# SCH_USB_hub_2024-10-12.net
KiCad netlist of a schematic drawn in EasyEDA
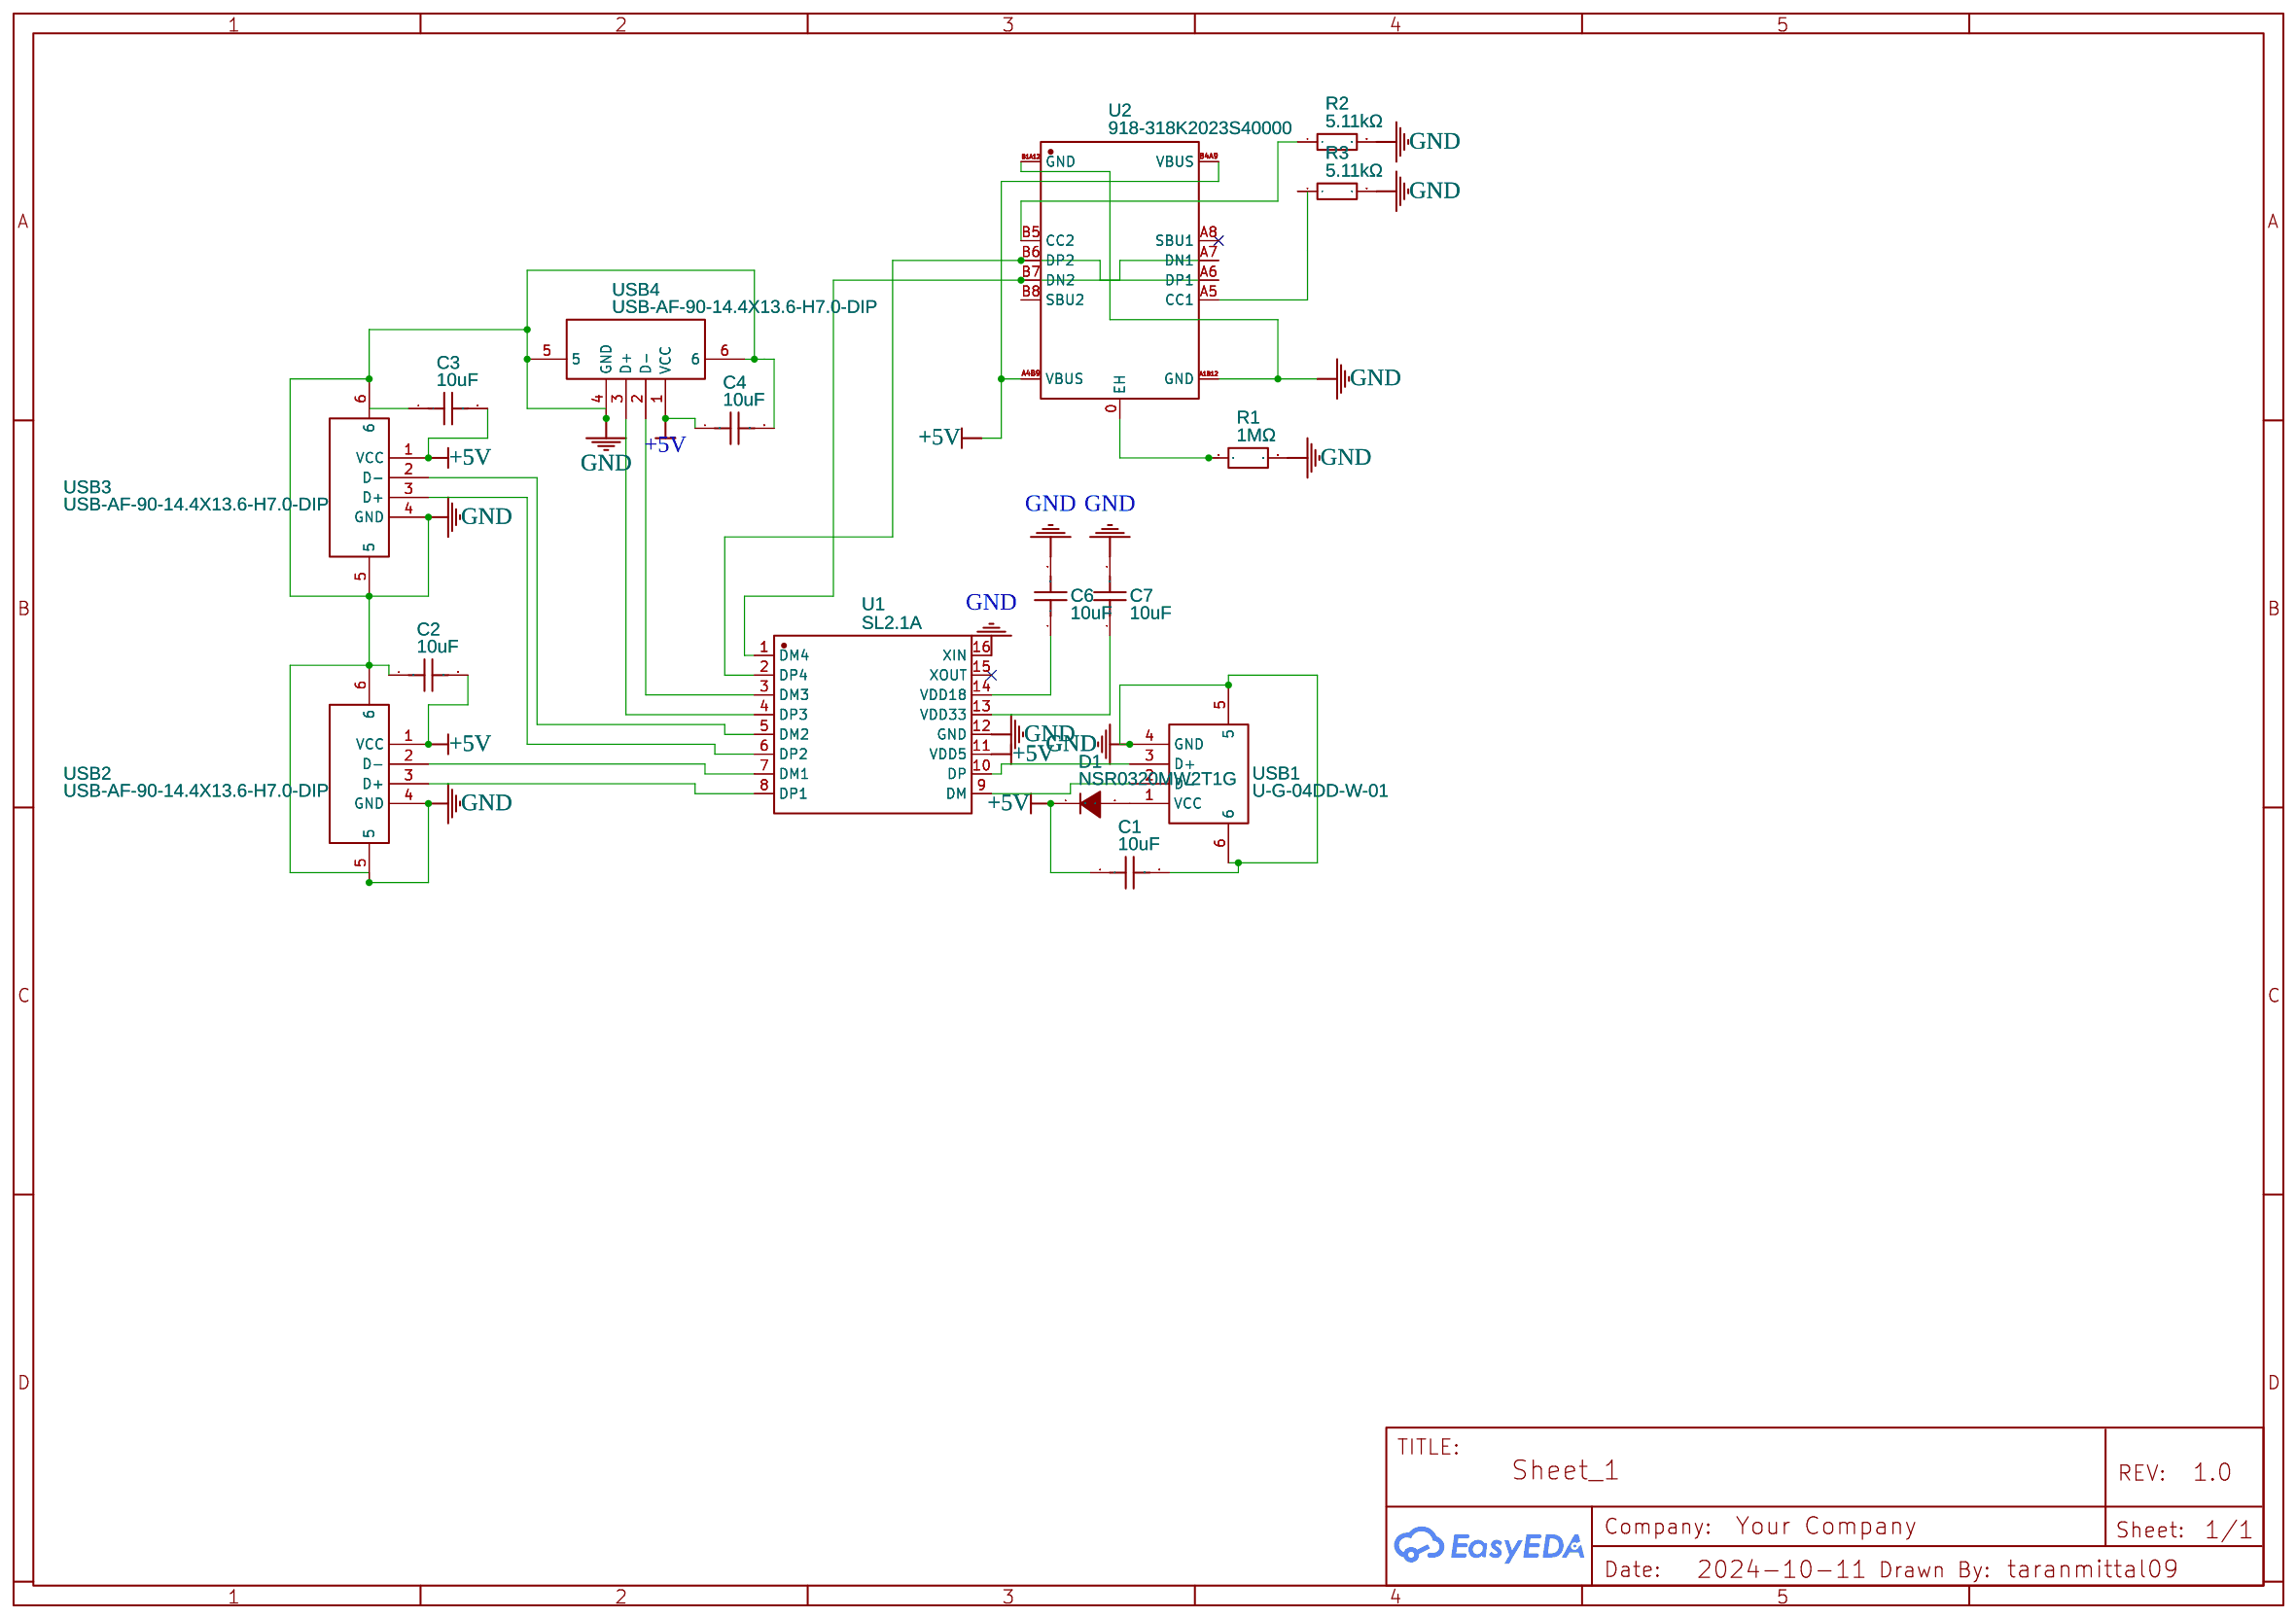
[diagram p0: schematic sheet]

(export (version "E")
  (design (tool "Eeschema 10.0.6"))
  (components
    (comp (ref "C1")
      (value "10uF")
      (fields
        (field (name "Manufacturer Part") "CL10A106KP8NNNC")
        (field (name "Manufacturer") "SAMSUNG(三星)")
      )
      (libsource (lib "") (part "CL10A106KP8NNNC"))
    )
    (comp (ref "C2")
      (value "10uF")
      (fields
        (field (name "Manufacturer Part") "CL10A106KP8NNNC")
        (field (name "Manufacturer") "SAMSUNG(三星)")
      )
      (libsource (lib "") (part "CL10A106KP8NNNC"))
    )
    (comp (ref "C3")
      (value "10uF")
      (fields
        (field (name "Manufacturer Part") "CL10A106KP8NNNC")
        (field (name "Manufacturer") "SAMSUNG(三星)")
      )
      (libsource (lib "") (part "CL10A106KP8NNNC"))
    )
    (comp (ref "C4")
      (value "10uF")
      (fields
        (field (name "Manufacturer Part") "CL10A106KP8NNNC")
        (field (name "Manufacturer") "SAMSUNG(三星)")
      )
      (libsource (lib "") (part "CL10A106KP8NNNC"))
    )
    (comp (ref "C6")
      (value "10uF")
      (fields
        (field (name "Manufacturer Part") "CL10A106KP8NNNC")
        (field (name "Manufacturer") "SAMSUNG(三星)")
      )
      (libsource (lib "") (part "CL10A106KP8NNNC_1"))
    )
    (comp (ref "C7")
      (value "10uF")
      (fields
        (field (name "Manufacturer Part") "CL10A106KP8NNNC")
        (field (name "Manufacturer") "SAMSUNG(三星)")
      )
      (libsource (lib "") (part "CL10A106KP8NNNC_1"))
    )
    (comp (ref "D1")
      (value "NSR0320MW2T1G")
      (fields (field (name "Manufacturer") "onsemi(安森美)"))
      (libsource (lib "") (part "NSR0320MW2T1G"))
    )
    (comp (ref "R1")
      (value "1MΩ")
      (fields
        (field (name "Manufacturer Part") "CRCW08051M00FKTB")
        (field (name "Manufacturer") "VISHAY(威世)")
      )
      (libsource (lib "") (part "CRCW08051M00FKTB"))
    )
    (comp (ref "R2")
      (value "5.11kΩ")
      (fields (field (name "Manufacturer Part") "RS-03K5111FT") (field (name "Manufacturer") "FH(风华)"))
      (libsource (lib "") (part "RS-03K5111FT"))
    )
    (comp (ref "R3")
      (value "5.11kΩ")
      (fields (field (name "Manufacturer Part") "RS-03K5111FT") (field (name "Manufacturer") "FH(风华)"))
      (libsource (lib "") (part "RS-03K5111FT"))
    )
    (comp (ref "U1")
      (value "SL2.1A")
      (fields (field (name "Manufacturer") "CoreChips(和芯润德)"))
      (libsource (lib "") (part "SL2.1A"))
    )
    (comp (ref "U2")
      (value "918-318K2023S40000")
      (fields (field (name "Manufacturer") "精拓金"))
      (libsource (lib "") (part "918-318K2023S40000"))
    )
    (comp (ref "USB1")
      (value "U-G-04DD-W-01")
      (fields (field (name "Manufacturer Part") "U-G-O4DD-W-1") (field (name "Manufacturer") "韩国韩荣"))
      (libsource (lib "") (part "U-G-04DD-W-01"))
    )
    (comp (ref "USB2")
      (value "USB-AF-90-14.4X13.6-H7.0-DIP")
      (fields (field (name "Manufacturer Part") "903-131A1011D10100") (field (name "Manufacturer") "精拓金"))
      (libsource (lib "") (part "USB-AF-90-14.4X13.6-H7.0-DIP"))
    )
    (comp (ref "USB3")
      (value "USB-AF-90-14.4X13.6-H7.0-DIP")
      (fields (field (name "Manufacturer Part") "903-131A1011D10100") (field (name "Manufacturer") "精拓金"))
      (libsource (lib "") (part "USB-AF-90-14.4X13.6-H7.0-DIP"))
    )
    (comp (ref "USB4")
      (value "USB-AF-90-14.4X13.6-H7.0-DIP")
      (fields (field (name "Manufacturer Part") "903-131A1011D10100") (field (name "Manufacturer") "精拓金"))
      (libsource (lib "") (part "USB-AF-90-14.4X13.6-H7.0-DIP_1"))
    )
  )
  (nets
    (net (code "1") (name "+5V") (class "Default")
      (node (ref "C1") (pin "1") (pinfunction "1_1") (pintype "unspecified"))
      (node (ref "C2") (pin "2") (pinfunction "2_2") (pintype "unspecified"))
      (node (ref "C3") (pin "2") (pinfunction "2_2") (pintype "unspecified"))
      (node (ref "C4") (pin "1") (pinfunction "1_1") (pintype "unspecified"))
      (node (ref "D1") (pin "1") (pinfunction "C_1") (pintype "unspecified"))
      (node (ref "U1") (pin "11") (pinfunction "VDD5_11") (pintype "unspecified"))
      (node (ref "U2") (pin "A4B9") (pinfunction "VBUS_A4B9") (pintype "unspecified"))
      (node (ref "U2") (pin "B4A9") (pinfunction "VBUS_B4A9") (pintype "unspecified"))
      (node (ref "USB2") (pin "1") (pinfunction "VCC_1") (pintype "unspecified"))
      (node (ref "USB3") (pin "1") (pinfunction "VCC_1") (pintype "unspecified"))
      (node (ref "USB4") (pin "1") (pinfunction "VCC_1") (pintype "unspecified"))
    )
    (net (code "2") (name "GND") (class "Default")
      (node (ref "C1") (pin "2") (pinfunction "2_2") (pintype "unspecified"))
      (node (ref "C2") (pin "1") (pinfunction "1_1") (pintype "unspecified"))
      (node (ref "C3") (pin "1") (pinfunction "1_1") (pintype "unspecified"))
      (node (ref "C4") (pin "2") (pinfunction "2_2") (pintype "unspecified"))
      (node (ref "C6") (pin "2") (pinfunction "2_2") (pintype "unspecified"))
      (node (ref "C7") (pin "2") (pinfunction "2_2") (pintype "unspecified"))
      (node (ref "R1") (pin "2") (pinfunction "2_2") (pintype "unspecified"))
      (node (ref "R2") (pin "2") (pinfunction "2_2") (pintype "input"))
      (node (ref "R3") (pin "2") (pinfunction "2_2") (pintype "input"))
      (node (ref "U1") (pin "12") (pinfunction "GND_12") (pintype "unspecified"))
      (node (ref "U1") (pin "16") (pinfunction "XIN_16") (pintype "unspecified"))
      (node (ref "U2") (pin "A1B12") (pinfunction "GND_A1B12") (pintype "unspecified"))
      (node (ref "U2") (pin "B1A12") (pinfunction "GND_B1A12") (pintype "unspecified"))
      (node (ref "USB1") (pin "4") (pinfunction "GND_4") (pintype "unspecified"))
      (node (ref "USB1") (pin "5") (pinfunction "5_5") (pintype "unspecified"))
      (node (ref "USB1") (pin "6") (pinfunction "6_6") (pintype "unspecified"))
      (node (ref "USB2") (pin "4") (pinfunction "GND_4") (pintype "unspecified"))
      (node (ref "USB2") (pin "5") (pinfunction "5_5") (pintype "unspecified"))
      (node (ref "USB2") (pin "6") (pinfunction "6_6") (pintype "unspecified"))
      (node (ref "USB3") (pin "4") (pinfunction "GND_4") (pintype "unspecified"))
      (node (ref "USB3") (pin "5") (pinfunction "5_5") (pintype "unspecified"))
      (node (ref "USB3") (pin "6") (pinfunction "6_6") (pintype "unspecified"))
      (node (ref "USB4") (pin "4") (pinfunction "GND_4") (pintype "unspecified"))
      (node (ref "USB4") (pin "5") (pinfunction "5_5") (pintype "unspecified"))
      (node (ref "USB4") (pin "6") (pinfunction "6_6") (pintype "unspecified"))
    )
    (net (code "3") (name "Net-(D1-A)") (class "Default")
      (node (ref "D1") (pin "2") (pinfunction "A_2") (pintype "unspecified"))
      (node (ref "USB1") (pin "1") (pinfunction "VCC_1") (pintype "unspecified"))
    )
    (net (code "4") (name "Net-(U1-DM)") (class "Default")
      (node (ref "U1") (pin "9") (pinfunction "DM_9") (pintype "unspecified"))
      (node (ref "USB1") (pin "2") (pinfunction "D-_2") (pintype "unspecified"))
    )
    (net (code "5") (name "Net-(U1-DM1)") (class "Default")
      (node (ref "U1") (pin "7") (pinfunction "DM1_7") (pintype "unspecified"))
      (node (ref "USB2") (pin "2") (pinfunction "D-_2") (pintype "unspecified"))
    )
    (net (code "6") (name "Net-(U1-DM2)") (class "Default")
      (node (ref "U1") (pin "5") (pinfunction "DM2_5") (pintype "unspecified"))
      (node (ref "USB3") (pin "2") (pinfunction "D-_2") (pintype "unspecified"))
    )
    (net (code "7") (name "Net-(U1-DM3)") (class "Default")
      (node (ref "U1") (pin "3") (pinfunction "DM3_3") (pintype "unspecified"))
      (node (ref "USB4") (pin "2") (pinfunction "D-_2") (pintype "unspecified"))
    )
    (net (code "8") (name "Net-(U1-DM4)") (class "Default")
      (node (ref "U1") (pin "1") (pinfunction "DM4_1") (pintype "unspecified"))
      (node (ref "U2") (pin "A7") (pinfunction "DN1_A7") (pintype "unspecified"))
      (node (ref "U2") (pin "B7") (pinfunction "DN2_B7") (pintype "unspecified"))
    )
    (net (code "9") (name "Net-(U1-DP)") (class "Default")
      (node (ref "U1") (pin "10") (pinfunction "DP_10") (pintype "unspecified"))
      (node (ref "USB1") (pin "3") (pinfunction "D+_3") (pintype "unspecified"))
    )
    (net (code "10") (name "Net-(U1-DP1)") (class "Default")
      (node (ref "U1") (pin "8") (pinfunction "DP1_8") (pintype "unspecified"))
      (node (ref "USB2") (pin "3") (pinfunction "D+_3") (pintype "unspecified"))
    )
    (net (code "11") (name "Net-(U1-DP2)") (class "Default")
      (node (ref "U1") (pin "6") (pinfunction "DP2_6") (pintype "unspecified"))
      (node (ref "USB3") (pin "3") (pinfunction "D+_3") (pintype "unspecified"))
    )
    (net (code "12") (name "Net-(U1-DP3)") (class "Default")
      (node (ref "U1") (pin "4") (pinfunction "DP3_4") (pintype "unspecified"))
      (node (ref "USB4") (pin "3") (pinfunction "D+_3") (pintype "unspecified"))
    )
    (net (code "13") (name "Net-(U1-DP4)") (class "Default")
      (node (ref "U1") (pin "2") (pinfunction "DP4_2") (pintype "unspecified"))
      (node (ref "U2") (pin "A6") (pinfunction "DP1_A6") (pintype "unspecified"))
      (node (ref "U2") (pin "B6") (pinfunction "DP2_B6") (pintype "unspecified"))
    )
    (net (code "14") (name "Net-(U1-VDD18)") (class "Default")
      (node (ref "C6") (pin "1") (pinfunction "1_1") (pintype "unspecified"))
      (node (ref "U1") (pin "14") (pinfunction "VDD18_14") (pintype "unspecified"))
    )
    (net (code "15") (name "Net-(U1-VDD33)") (class "Default")
      (node (ref "C7") (pin "1") (pinfunction "1_1") (pintype "unspecified"))
      (node (ref "U1") (pin "13") (pinfunction "VDD33_13") (pintype "unspecified"))
    )
    (net (code "16") (name "Net-(U2-CC1)") (class "Default")
      (node (ref "R3") (pin "1") (pinfunction "1_1") (pintype "input"))
      (node (ref "U2") (pin "A5") (pinfunction "CC1_A5") (pintype "unspecified"))
    )
    (net (code "17") (name "Net-(U2-CC2)") (class "Default")
      (node (ref "R2") (pin "1") (pinfunction "1_1") (pintype "input"))
      (node (ref "U2") (pin "B5") (pinfunction "CC2_B5") (pintype "unspecified"))
    )
    (net (code "18") (name "Net-(U2-EH)") (class "Default")
      (node (ref "R1") (pin "1") (pinfunction "1_1") (pintype "unspecified"))
      (node (ref "U2") (pin "0") (pinfunction "EH_0") (pintype "unspecified"))
    )
    (net (code "19") (name "unconnected-(U1-XOUT-Pad15)") (class "Default")
      (node (ref "U1") (pin "15") (pinfunction "XOUT_15") (pintype "unspecified+no_connect"))
    )
    (net (code "20") (name "unconnected-(U2-SBU1-PadA8)") (class "Default")
      (node (ref "U2") (pin "A8") (pinfunction "SBU1_A8") (pintype "unspecified+no_connect"))
    )
    (net (code "21") (name "unconnected-(U2-SBU2-PadB8)") (class "Default")
      (node (ref "U2") (pin "B8") (pinfunction "SBU2_B8") (pintype "unspecified"))
    )
  )
)
